# SCH_Arduino-Train-v_2_2026-09-02.net
KiCad netlist of a schematic drawn in EasyEDA
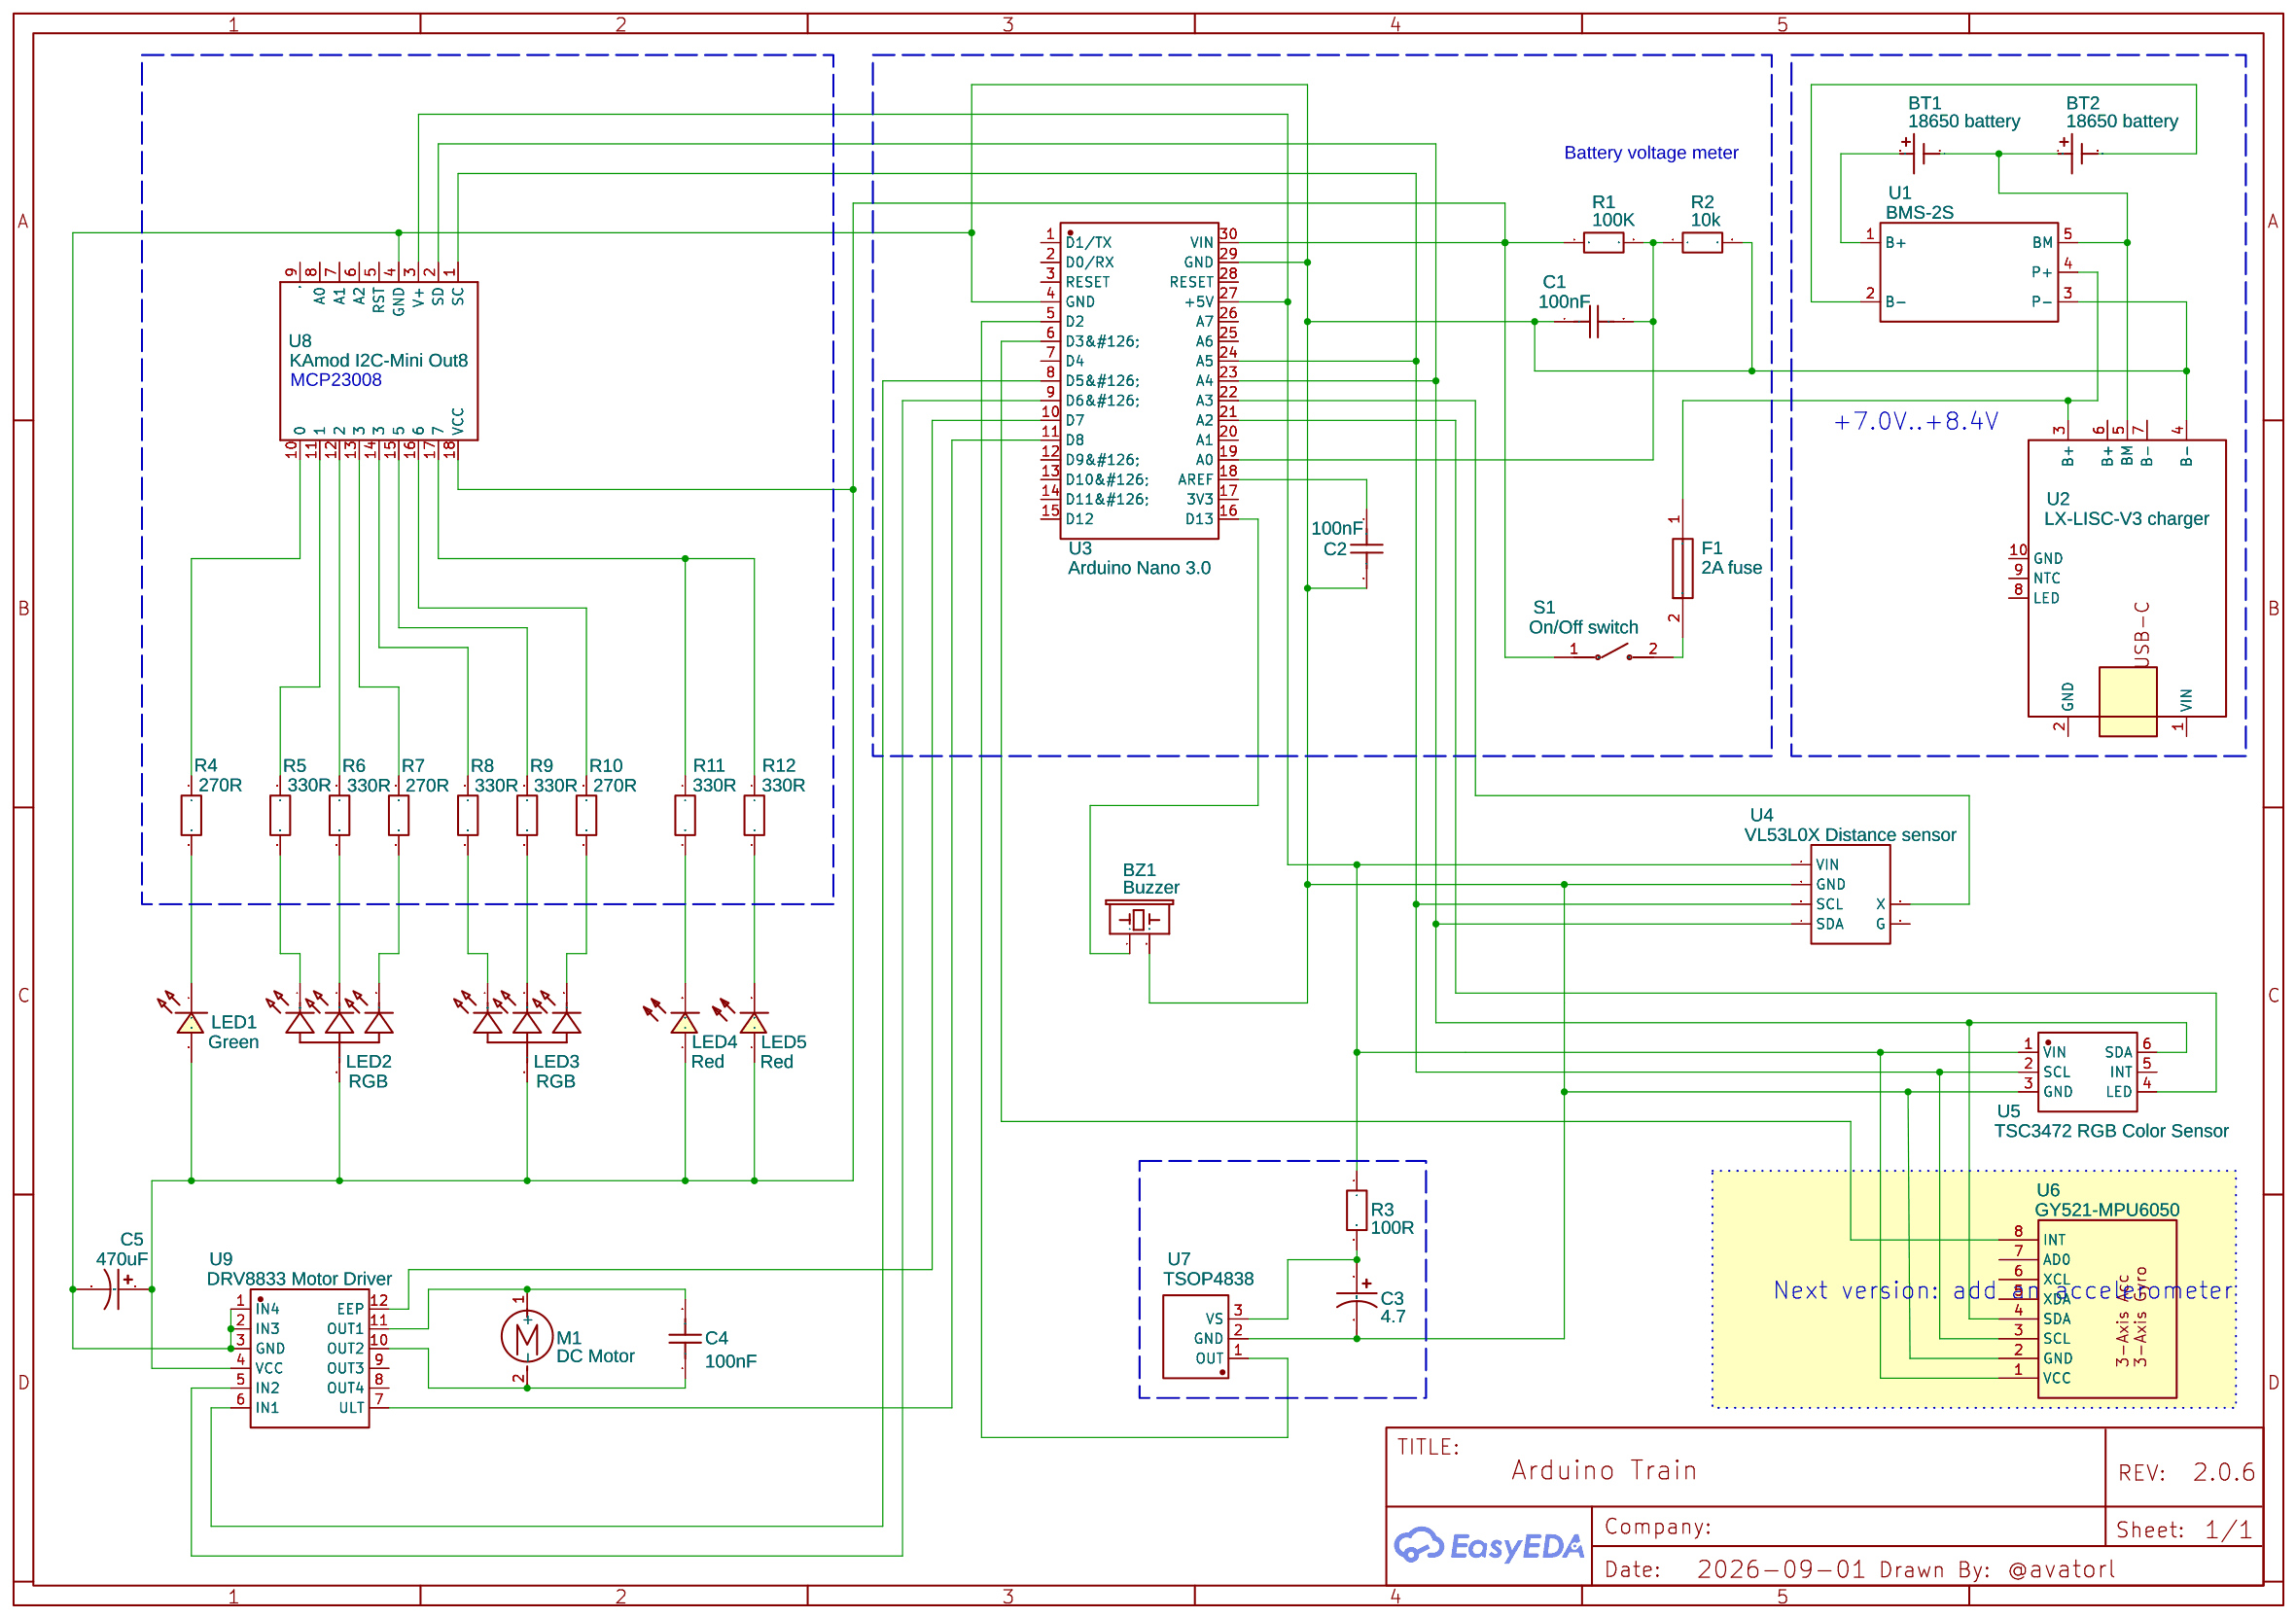
[diagram p0: schematic sheet]

(export (version "E")
  (design (tool "Eeschema 10.0.6"))
  (components
    (comp (ref "BT1") (value "18650 battery") (libsource (lib "") (part "BAT-18650")))
    (comp (ref "BT2") (value "18650 battery") (libsource (lib "") (part "BAT-18650")))
    (comp (ref "BZ1") (value "Buzzer") (libsource (lib "") (part "BUZZER")))
    (comp (ref "C1") (value "100nF") (libsource (lib "") (part "C_0603_US")))
    (comp (ref "C2") (value "100nF") (libsource (lib "") (part "C_0603_US_1")))
    (comp (ref "C3")
      (value "4.7")
      (fields (field (name "Manufacturer Part") "B32672P5105J000") (field (name "Manufacturer") "TDK"))
      (libsource (lib "") (part "C_Tan_SMD_A_US_1"))
    )
    (comp (ref "C4") (value "100nF") (libsource (lib "") (part "C_0603_US_2")))
    (comp (ref "C5")
      (value "470uF")
      (fields (field (name "Manufacturer Part") "B32672P5105J000") (field (name "Manufacturer") "TDK"))
      (libsource (lib "") (part "C_Tan_SMD_A_US"))
    )
    (comp (ref "F1") (value "2A fuse") (libsource (lib "") (part "FUSE BLADE_PCB_MOUNT COPY")))
    (comp (ref "LED1")
      (value "Green")
      (fields (field (name "Manufacturer Part") "LED三色(Red,Yellow,Green)"))
      (libsource (lib "") (part "LED (GREEN)"))
    )
    (comp (ref "LED2")
      (value "RGB")
      (fields (field (name "Manufacturer Part") "3528反贴RGB 6028反贴RGB 缺口蓝色"))
      (libsource (lib "") (part "3528RGB 6028RGB"))
    )
    (comp (ref "LED3")
      (value "RGB")
      (fields (field (name "Manufacturer Part") "3528反贴RGB 6028反贴RGB 缺口蓝色"))
      (libsource (lib "") (part "3528RGB 6028RGB"))
    )
    (comp (ref "LED4")
      (value "Red")
      (fields (field (name "Manufacturer Part") "LED-3mm红"))
      (libsource (lib "") (part "LED"))
    )
    (comp (ref "LED5")
      (value "Red")
      (fields (field (name "Manufacturer Part") "LED-3mm红"))
      (libsource (lib "") (part "LED"))
    )
    (comp (ref "M1") (value "DC Motor") (libsource (lib "") (part "Motor_DC")))
    (comp (ref "R1") (value "100K") (libsource (lib "") (part "R_0603_EU")))
    (comp (ref "R2") (value "10k") (libsource (lib "") (part "R_0603_EU")))
    (comp (ref "R3") (value "100R") (libsource (lib "") (part "R_0603_EU_1")))
    (comp (ref "R4") (value "270R") (libsource (lib "") (part "R_0603_EU_1")))
    (comp (ref "R5") (value "330R") (libsource (lib "") (part "R_0603_EU_1")))
    (comp (ref "R6") (value "330R") (libsource (lib "") (part "R_0603_EU_1")))
    (comp (ref "R7") (value "270R") (libsource (lib "") (part "R_0603_EU_1")))
    (comp (ref "R8") (value "330R") (libsource (lib "") (part "R_0603_EU_1")))
    (comp (ref "R9") (value "330R") (libsource (lib "") (part "R_0603_EU_1")))
    (comp (ref "R10") (value "270R") (libsource (lib "") (part "R_0603_EU_1")))
    (comp (ref "R11") (value "330R") (libsource (lib "") (part "R_0603_EU_1")))
    (comp (ref "R12") (value "330R") (libsource (lib "") (part "R_0603_EU_1")))
    (comp (ref "S1")
      (value "On/Off switch")
      (fields (field (name "Manufacturer Part") "BUTTON"))
      (libsource (lib "") (part "BUTTON"))
    )
    (comp (ref "U1")
      (value "BMS-2S")
      (fields (field (name "Manufacturer Part") "HX-2S-D01"))
      (libsource (lib "") (part "2S 3A-10A Lithium Li-ion 18650 Battery BMS Protection PCB Board 7.4v/8.4V"))
    )
    (comp (ref "U2") (value "LX-LISC-V3 charger") (libsource (lib "") (part "LX-LISC-V1")))
    (comp (ref "U3")
      (value "Arduino Nano 3.0")
      (fields (field (name "Manufacturer Part") "ARDUINO_NANO"))
      (libsource (lib "") (part "ARDUINO_NANO"))
    )
    (comp (ref "U4")
      (value "VL53L0X Distance sensor")
      (fields (field (name "Manufacturer Part") "IDC Box 2X4 2.54MM") (field (name "Manufacturer") "BOOMELE"))
      (libsource (lib "") (part "GYUL53L0X_UPDATED final"))
    )
    (comp (ref "U5")
      (value "TSC3472 RGB Color Sensor")
      (fields (field (name "Manufacturer Part") "TCS34725FN") (field (name "Manufacturer") "ams(艾迈斯半导体)"))
      (libsource (lib "") (part "TCS34725FN"))
    )
    (comp (ref "U6") (value "GY521-MPU6050") (libsource (lib "") (part "GY521-MPU6050")))
    (comp (ref "U7")
      (value "TSOP4838")
      (fields (field (name "Manufacturer") "VISHAY(威世)"))
      (libsource (lib "") (part "TSOP4838"))
    )
    (comp (ref "U8") (value "KAmod I2C-Mini Out8") (libsource (lib "") (part "MCP23008P")))
    (comp (ref "U9")
      (value "DRV8833 Motor Driver")
      (fields (field (name "Manufacturer Part") "DRV8833"))
      (libsource (lib "") (part "DRV8833 - Motor Driver"))
    )
  )
  (nets
    (net (code "1") (name "Net-(BT1-N)") (class "Default")
      (node (ref "BT1") (pin "2") (pinfunction "N_2") (pintype "bidirectional"))
      (node (ref "BT2") (pin "1") (pinfunction "P_1") (pintype "bidirectional"))
      (node (ref "U1") (pin "5") (pinfunction "BM_5") (pintype "unspecified"))
      (node (ref "U2") (pin "5") (pinfunction "BM_5") (pintype "unspecified"))
    )
    (net (code "2") (name "Net-(BT1-P)") (class "Default")
      (node (ref "BT1") (pin "1") (pinfunction "P_1") (pintype "bidirectional"))
      (node (ref "U1") (pin "1") (pinfunction "B+_1") (pintype "unspecified"))
    )
    (net (code "3") (name "Net-(BT2-N)") (class "Default")
      (node (ref "BT2") (pin "2") (pinfunction "N_2") (pintype "bidirectional"))
      (node (ref "U1") (pin "2") (pinfunction "B-_2") (pintype "unspecified"))
    )
    (net (code "4") (name "Net-(F1-Pad2)") (class "Default")
      (node (ref "F1") (pin "2") (pinfunction "2_2") (pintype "unspecified"))
      (node (ref "S1") (pin "2") (pinfunction "2_2") (pintype "unspecified"))
    )
    (net (code "5") (name "Net-(LED1-Pad1)") (class "Default")
      (node (ref "LED1") (pin "1") (pinfunction "1_1") (pintype "unspecified"))
      (node (ref "R4") (pin "2") (pinfunction "2_2") (pintype "unspecified"))
    )
    (net (code "6") (name "Net-(LED2-A)") (class "Default")
      (node (ref "C5") (pin "1") (pinfunction "1_1") (pintype "unspecified"))
      (node (ref "LED1") (pin "2") (pinfunction "2_2") (pintype "unspecified"))
      (node (ref "LED2") (pin "3") (pinfunction "A_3") (pintype "unspecified"))
      (node (ref "LED3") (pin "3") (pinfunction "A_3") (pintype "unspecified"))
      (node (ref "LED4") (pin "1") (pinfunction "1_1") (pintype "unspecified"))
      (node (ref "LED5") (pin "1") (pinfunction "1_1") (pintype "unspecified"))
      (node (ref "R1") (pin "1") (pinfunction "1_1") (pintype "unspecified"))
      (node (ref "S1") (pin "1") (pinfunction "1_1") (pintype "unspecified"))
      (node (ref "U3") (pin "30") (pinfunction "VIN_30") (pintype "unspecified"))
      (node (ref "U8") (pin "18") (pinfunction "VCC_18") (pintype "passive"))
      (node (ref "U9") (pin "4") (pinfunction "VCC_4") (pintype "unspecified"))
    )
    (net (code "7") (name "Net-(LED2-B)") (class "Default")
      (node (ref "LED2") (pin "1") (pinfunction "B_1") (pintype "unspecified"))
      (node (ref "R6") (pin "2") (pinfunction "2_2") (pintype "unspecified"))
    )
    (net (code "8") (name "Net-(LED2-G)") (class "Default")
      (node (ref "LED2") (pin "4") (pinfunction "G_4") (pintype "unspecified"))
      (node (ref "R5") (pin "2") (pinfunction "2_2") (pintype "unspecified"))
    )
    (net (code "9") (name "Net-(LED2-R)") (class "Default")
      (node (ref "LED2") (pin "2") (pinfunction "R_2") (pintype "unspecified"))
      (node (ref "R7") (pin "2") (pinfunction "2_2") (pintype "unspecified"))
    )
    (net (code "10") (name "Net-(LED3-B)") (class "Default")
      (node (ref "LED3") (pin "1") (pinfunction "B_1") (pintype "unspecified"))
      (node (ref "R9") (pin "2") (pinfunction "2_2") (pintype "unspecified"))
    )
    (net (code "11") (name "Net-(LED3-G)") (class "Default")
      (node (ref "LED3") (pin "4") (pinfunction "G_4") (pintype "unspecified"))
      (node (ref "R8") (pin "2") (pinfunction "2_2") (pintype "unspecified"))
    )
    (net (code "12") (name "Net-(LED3-R)") (class "Default")
      (node (ref "LED3") (pin "2") (pinfunction "R_2") (pintype "unspecified"))
      (node (ref "R10") (pin "2") (pinfunction "2_2") (pintype "unspecified"))
    )
    (net (code "13") (name "Net-(LED4-Pad2)") (class "Default")
      (node (ref "LED4") (pin "2") (pinfunction "2_2") (pintype "unspecified"))
      (node (ref "R11") (pin "2") (pinfunction "2_2") (pintype "unspecified"))
    )
    (net (code "14") (name "Net-(LED5-Pad2)") (class "Default")
      (node (ref "LED5") (pin "2") (pinfunction "2_2") (pintype "unspecified"))
      (node (ref "R12") (pin "2") (pinfunction "2_2") (pintype "unspecified"))
    )
    (net (code "15") (name "Net-(M1-+)") (class "Default")
      (node (ref "C4") (pin "2") (pinfunction "2_2") (pintype "unspecified"))
      (node (ref "M1") (pin "1") (pinfunction "+_1") (pintype "unspecified"))
      (node (ref "U9") (pin "11") (pinfunction "OUT1_11") (pintype "unspecified"))
    )
    (net (code "16") (name "Net-(M1--)") (class "Default")
      (node (ref "C4") (pin "1") (pinfunction "1_1") (pintype "unspecified"))
      (node (ref "M1") (pin "2") (pinfunction "-_2") (pintype "unspecified"))
      (node (ref "U9") (pin "10") (pinfunction "OUT2_10") (pintype "unspecified"))
    )
    (net (code "17") (name "Net-(R7-Pad1)") (class "Default")
      (node (ref "R7") (pin "1") (pinfunction "1_1") (pintype "unspecified"))
      (node (ref "U8") (pin "13") (pinfunction "3_13") (pintype "unspecified"))
    )
    (net (code "18") (name "Net-(R8-Pad1)") (class "Default")
      (node (ref "R8") (pin "1") (pinfunction "1_1") (pintype "unspecified"))
      (node (ref "U8") (pin "14") (pinfunction "3_14") (pintype "unspecified"))
    )
    (net (code "19") (name "Net-(U1-P+)") (class "Default")
      (node (ref "F1") (pin "1") (pinfunction "1_1") (pintype "unspecified"))
      (node (ref "U1") (pin "4") (pinfunction "P+_4") (pintype "unspecified"))
      (node (ref "U2") (pin "3") (pinfunction "B+_3") (pintype "unspecified"))
    )
    (net (code "20") (name "Net-(U1-P-)") (class "Default")
      (node (ref "BZ1") (pin "2") (pinfunction "2_2") (pintype "unspecified"))
      (node (ref "C1") (pin "1") (pinfunction "1_1") (pintype "unspecified"))
      (node (ref "C2") (pin "2") (pinfunction "2_2") (pintype "unspecified"))
      (node (ref "C3") (pin "2") (pinfunction "2_2") (pintype "unspecified"))
      (node (ref "C5") (pin "2") (pinfunction "2_2") (pintype "unspecified"))
      (node (ref "R2") (pin "2") (pinfunction "2_2") (pintype "unspecified"))
      (node (ref "U1") (pin "3") (pinfunction "P-_3") (pintype "unspecified"))
      (node (ref "U2") (pin "4") (pinfunction "B-_4") (pintype "unspecified"))
      (node (ref "U3") (pin "29") (pinfunction "GND_29") (pintype "unspecified"))
      (node (ref "U3") (pin "4") (pinfunction "GND_4") (pintype "unspecified"))
      (node (ref "U4") (pin "3") (pinfunction "GND_3") (pintype "unspecified"))
      (node (ref "U5") (pin "3") (pinfunction "GND_3") (pintype "unspecified"))
      (node (ref "U6") (pin "2") (pinfunction "GND_2") (pintype "passive"))
      (node (ref "U7") (pin "2") (pinfunction "GND_2") (pintype "unspecified"))
      (node (ref "U8") (pin "4") (pinfunction "GND_4") (pintype "input"))
      (node (ref "U9") (pin "1") (pinfunction "IN4_1") (pintype "unspecified"))
      (node (ref "U9") (pin "2") (pinfunction "IN3_2") (pintype "unspecified"))
      (node (ref "U9") (pin "3") (pinfunction "GND_3") (pintype "unspecified"))
    )
    (net (code "21") (name "Net-(U3-+5V)") (class "Default")
      (node (ref "R3") (pin "1") (pinfunction "1_1") (pintype "unspecified"))
      (node (ref "U3") (pin "27") (pinfunction "+5V_27") (pintype "unspecified"))
      (node (ref "U4") (pin "1") (pinfunction "VIN_1") (pintype "unspecified"))
      (node (ref "U5") (pin "1") (pinfunction "VIN_1") (pintype "unspecified"))
      (node (ref "U6") (pin "1") (pinfunction "VCC_1") (pintype "passive"))
      (node (ref "U8") (pin "3") (pinfunction "V+_3") (pintype "input"))
    )
    (net (code "22") (name "Net-(U3-A0)") (class "Default")
      (node (ref "C1") (pin "2") (pinfunction "2_2") (pintype "unspecified"))
      (node (ref "R1") (pin "2") (pinfunction "2_2") (pintype "unspecified"))
      (node (ref "R2") (pin "1") (pinfunction "1_1") (pintype "unspecified"))
      (node (ref "U3") (pin "19") (pinfunction "A0_19") (pintype "unspecified"))
    )
    (net (code "23") (name "Net-(U3-A2)") (class "Default")
      (node (ref "U3") (pin "21") (pinfunction "A2_21") (pintype "unspecified"))
      (node (ref "U5") (pin "4") (pinfunction "LED_4") (pintype "unspecified"))
    )
    (net (code "24") (name "Net-(U3-A3)") (class "Default")
      (node (ref "U3") (pin "22") (pinfunction "A3_22") (pintype "unspecified"))
      (node (ref "U4") (pin "6") (pinfunction "X_6") (pintype "unspecified"))
    )
    (net (code "25") (name "Net-(U3-A4)") (class "Default")
      (node (ref "U3") (pin "23") (pinfunction "A4_23") (pintype "unspecified"))
      (node (ref "U4") (pin "7") (pinfunction "SDA_7") (pintype "unspecified"))
      (node (ref "U5") (pin "6") (pinfunction "SDA_6") (pintype "unspecified"))
      (node (ref "U6") (pin "4") (pinfunction "SDA_4") (pintype "bidirectional"))
      (node (ref "U8") (pin "2") (pinfunction "SD_2") (pintype "unspecified"))
    )
    (net (code "26") (name "Net-(U3-A5)") (class "Default")
      (node (ref "U3") (pin "24") (pinfunction "A5_24") (pintype "unspecified"))
      (node (ref "U4") (pin "5") (pinfunction "SCL_5") (pintype "unspecified"))
      (node (ref "U5") (pin "2") (pinfunction "SCL_2") (pintype "unspecified"))
      (node (ref "U6") (pin "3") (pinfunction "SCL_3") (pintype "bidirectional"))
      (node (ref "U8") (pin "1") (pinfunction "SC_1") (pintype "input"))
    )
    (net (code "27") (name "Net-(U3-AREF)") (class "Default")
      (node (ref "C2") (pin "1") (pinfunction "1_1") (pintype "unspecified"))
      (node (ref "U3") (pin "18") (pinfunction "AREF_18") (pintype "unspecified"))
    )
    (net (code "28") (name "Net-(U3-D2)") (class "Default")
      (node (ref "U3") (pin "5") (pinfunction "D2_5") (pintype "unspecified"))
      (node (ref "U7") (pin "1") (pinfunction "OUT_1") (pintype "unspecified"))
    )
    (net (code "29") (name "Net-(U3-D3&#126;)") (class "Default")
      (node (ref "U3") (pin "6") (pinfunction "D3&#126;_6") (pintype "unspecified"))
      (node (ref "U6") (pin "8") (pinfunction "INT_8") (pintype "output"))
    )
    (net (code "30") (name "Net-(U3-D5&#126;)") (class "Default")
      (node (ref "U3") (pin "8") (pinfunction "D5&#126;_8") (pintype "unspecified"))
      (node (ref "U9") (pin "6") (pinfunction "IN1_6") (pintype "unspecified"))
    )
    (net (code "31") (name "Net-(U3-D6&#126;)") (class "Default")
      (node (ref "U3") (pin "9") (pinfunction "D6&#126;_9") (pintype "unspecified"))
      (node (ref "U9") (pin "5") (pinfunction "IN2_5") (pintype "unspecified"))
    )
    (net (code "32") (name "Net-(U3-D7)") (class "Default")
      (node (ref "U3") (pin "10") (pinfunction "D7_10") (pintype "unspecified"))
      (node (ref "U9") (pin "12") (pinfunction "EEP_12") (pintype "unspecified"))
    )
    (net (code "33") (name "Net-(U3-D8)") (class "Default")
      (node (ref "U3") (pin "11") (pinfunction "D8_11") (pintype "unspecified"))
      (node (ref "U9") (pin "7") (pinfunction "ULT_7") (pintype "unspecified"))
    )
    (net (code "34") (name "Net-(U3-D13)") (class "Default")
      (node (ref "BZ1") (pin "1") (pinfunction "1_1") (pintype "unspecified"))
      (node (ref "U3") (pin "16") (pinfunction "D13_16") (pintype "unspecified"))
    )
    (net (code "35") (name "Net-(U7-VS)") (class "Default")
      (node (ref "C3") (pin "1") (pinfunction "1_1") (pintype "unspecified"))
      (node (ref "R3") (pin "2") (pinfunction "2_2") (pintype "unspecified"))
      (node (ref "U7") (pin "3") (pinfunction "VS_3") (pintype "unspecified"))
    )
    (net (code "36") (name "Net-(U8-0)") (class "Default")
      (node (ref "R4") (pin "1") (pinfunction "1_1") (pintype "unspecified"))
      (node (ref "U8") (pin "10") (pinfunction "0_10") (pintype "unspecified"))
    )
    (net (code "37") (name "Net-(U8-1)") (class "Default")
      (node (ref "R5") (pin "1") (pinfunction "1_1") (pintype "unspecified"))
      (node (ref "U8") (pin "11") (pinfunction "1_11") (pintype "unspecified"))
    )
    (net (code "38") (name "Net-(U8-2)") (class "Default")
      (node (ref "R6") (pin "1") (pinfunction "1_1") (pintype "unspecified"))
      (node (ref "U8") (pin "12") (pinfunction "2_12") (pintype "unspecified"))
    )
    (net (code "39") (name "Net-(U8-5)") (class "Default")
      (node (ref "R9") (pin "1") (pinfunction "1_1") (pintype "unspecified"))
      (node (ref "U8") (pin "15") (pinfunction "5_15") (pintype "unspecified"))
    )
    (net (code "40") (name "Net-(U8-6)") (class "Default")
      (node (ref "R10") (pin "1") (pinfunction "1_1") (pintype "unspecified"))
      (node (ref "U8") (pin "16") (pinfunction "6_16") (pintype "unspecified"))
    )
    (net (code "41") (name "Net-(U8-7)") (class "Default")
      (node (ref "R11") (pin "1") (pinfunction "1_1") (pintype "unspecified"))
      (node (ref "R12") (pin "1") (pinfunction "1_1") (pintype "unspecified"))
      (node (ref "U8") (pin "17") (pinfunction "7_17") (pintype "unspecified"))
    )
    (net (code "42") (name "unconnected-(U2-B+-Pad6)") (class "Default")
      (node (ref "U2") (pin "6") (pinfunction "B+_6") (pintype "unspecified"))
    )
    (net (code "43") (name "unconnected-(U2-B--Pad7)") (class "Default")
      (node (ref "U2") (pin "7") (pinfunction "B-_7") (pintype "unspecified"))
    )
    (net (code "44") (name "unconnected-(U2-GND-Pad2)") (class "Default")
      (node (ref "U2") (pin "2") (pinfunction "GND_2") (pintype "unspecified"))
    )
    (net (code "45") (name "unconnected-(U2-GND-Pad10)") (class "Default")
      (node (ref "U2") (pin "10") (pinfunction "GND_10") (pintype "unspecified"))
    )
    (net (code "46") (name "unconnected-(U2-LED-Pad8)") (class "Default")
      (node (ref "U2") (pin "8") (pinfunction "LED_8") (pintype "unspecified"))
    )
    (net (code "47") (name "unconnected-(U2-NTC-Pad9)") (class "Default")
      (node (ref "U2") (pin "9") (pinfunction "NTC_9") (pintype "unspecified"))
    )
    (net (code "48") (name "unconnected-(U2-VIN-Pad1)") (class "Default")
      (node (ref "U2") (pin "1") (pinfunction "VIN_1") (pintype "unspecified"))
    )
    (net (code "49") (name "unconnected-(U3-3V3-Pad17)") (class "Default")
      (node (ref "U3") (pin "17") (pinfunction "3V3_17") (pintype "unspecified"))
    )
    (net (code "50") (name "unconnected-(U3-A1-Pad20)") (class "Default")
      (node (ref "U3") (pin "20") (pinfunction "A1_20") (pintype "unspecified"))
    )
    (net (code "51") (name "unconnected-(U3-A6-Pad25)") (class "Default")
      (node (ref "U3") (pin "25") (pinfunction "A6_25") (pintype "unspecified"))
    )
    (net (code "52") (name "unconnected-(U3-A7-Pad26)") (class "Default")
      (node (ref "U3") (pin "26") (pinfunction "A7_26") (pintype "unspecified"))
    )
    (net (code "53") (name "unconnected-(U3-D0{slash}RX-Pad2)") (class "Default")
      (node (ref "U3") (pin "2") (pinfunction "D0/RX_2") (pintype "unspecified"))
    )
    (net (code "54") (name "unconnected-(U3-D1{slash}TX-Pad1)") (class "Default")
      (node (ref "U3") (pin "1") (pinfunction "D1/TX_1") (pintype "unspecified"))
    )
    (net (code "55") (name "unconnected-(U3-D4-Pad7)") (class "Default")
      (node (ref "U3") (pin "7") (pinfunction "D4_7") (pintype "unspecified"))
    )
    (net (code "56") (name "unconnected-(U3-D9&#126;-Pad12)") (class "Default")
      (node (ref "U3") (pin "12") (pinfunction "D9&#126;_12") (pintype "unspecified"))
    )
    (net (code "57") (name "unconnected-(U3-D10&#126;-Pad13)") (class "Default")
      (node (ref "U3") (pin "13") (pinfunction "D10&#126;_13") (pintype "unspecified"))
    )
    (net (code "58") (name "unconnected-(U3-D11&#126;-Pad14)") (class "Default")
      (node (ref "U3") (pin "14") (pinfunction "D11&#126;_14") (pintype "unspecified"))
    )
    (net (code "59") (name "unconnected-(U3-D12-Pad15)") (class "Default")
      (node (ref "U3") (pin "15") (pinfunction "D12_15") (pintype "unspecified"))
    )
    (net (code "60") (name "unconnected-(U3-RESET-Pad3)") (class "Default")
      (node (ref "U3") (pin "3") (pinfunction "RESET_3") (pintype "unspecified"))
    )
    (net (code "61") (name "unconnected-(U3-RESET-Pad28)") (class "Default")
      (node (ref "U3") (pin "28") (pinfunction "RESET_28") (pintype "unspecified"))
    )
    (net (code "62") (name "unconnected-(U4-G-Pad8)") (class "Default")
      (node (ref "U4") (pin "8") (pinfunction "G_8") (pintype "unspecified"))
    )
    (net (code "63") (name "unconnected-(U5-INT-Pad5)") (class "Default")
      (node (ref "U5") (pin "5") (pinfunction "INT_5") (pintype "unspecified"))
    )
    (net (code "64") (name "unconnected-(U6-AD0-Pad7)") (class "Default")
      (node (ref "U6") (pin "7") (pinfunction "AD0_7") (pintype "input"))
    )
    (net (code "65") (name "unconnected-(U6-XCL-Pad6)") (class "Default")
      (node (ref "U6") (pin "6") (pinfunction "XCL_6") (pintype "bidirectional"))
    )
    (net (code "66") (name "unconnected-(U6-XDA-Pad5)") (class "Default")
      (node (ref "U6") (pin "5") (pinfunction "XDA_5") (pintype "bidirectional"))
    )
    (net (code "67") (name "unconnected-(U8-A0-Pad8)") (class "Default")
      (node (ref "U8") (pin "8") (pinfunction "A0_8") (pintype "output"))
    )
    (net (code "68") (name "unconnected-(U8-A1-Pad7)") (class "Default")
      (node (ref "U8") (pin "7") (pinfunction "A1_7") (pintype "unspecified"))
    )
    (net (code "69") (name "unconnected-(U8-A2-Pad6)") (class "Default")
      (node (ref "U8") (pin "6") (pinfunction "A2_6") (pintype "input"))
    )
    (net (code "70") (name "unconnected-(U8-NC-Pad9)") (class "Default")
      (node (ref "U8") (pin "9") (pinfunction "NC_9") (pintype "passive"))
    )
    (net (code "71") (name "unconnected-(U8-RST-Pad5)") (class "Default")
      (node (ref "U8") (pin "5") (pinfunction "RST_5") (pintype "input"))
    )
    (net (code "72") (name "unconnected-(U9-OUT3-Pad9)") (class "Default")
      (node (ref "U9") (pin "9") (pinfunction "OUT3_9") (pintype "unspecified"))
    )
    (net (code "73") (name "unconnected-(U9-OUT4-Pad8)") (class "Default")
      (node (ref "U9") (pin "8") (pinfunction "OUT4_8") (pintype "unspecified"))
    )
  )
)
